# FluxamasynthShield.net
KiCad netlist of a schematic drawn in EAGLE
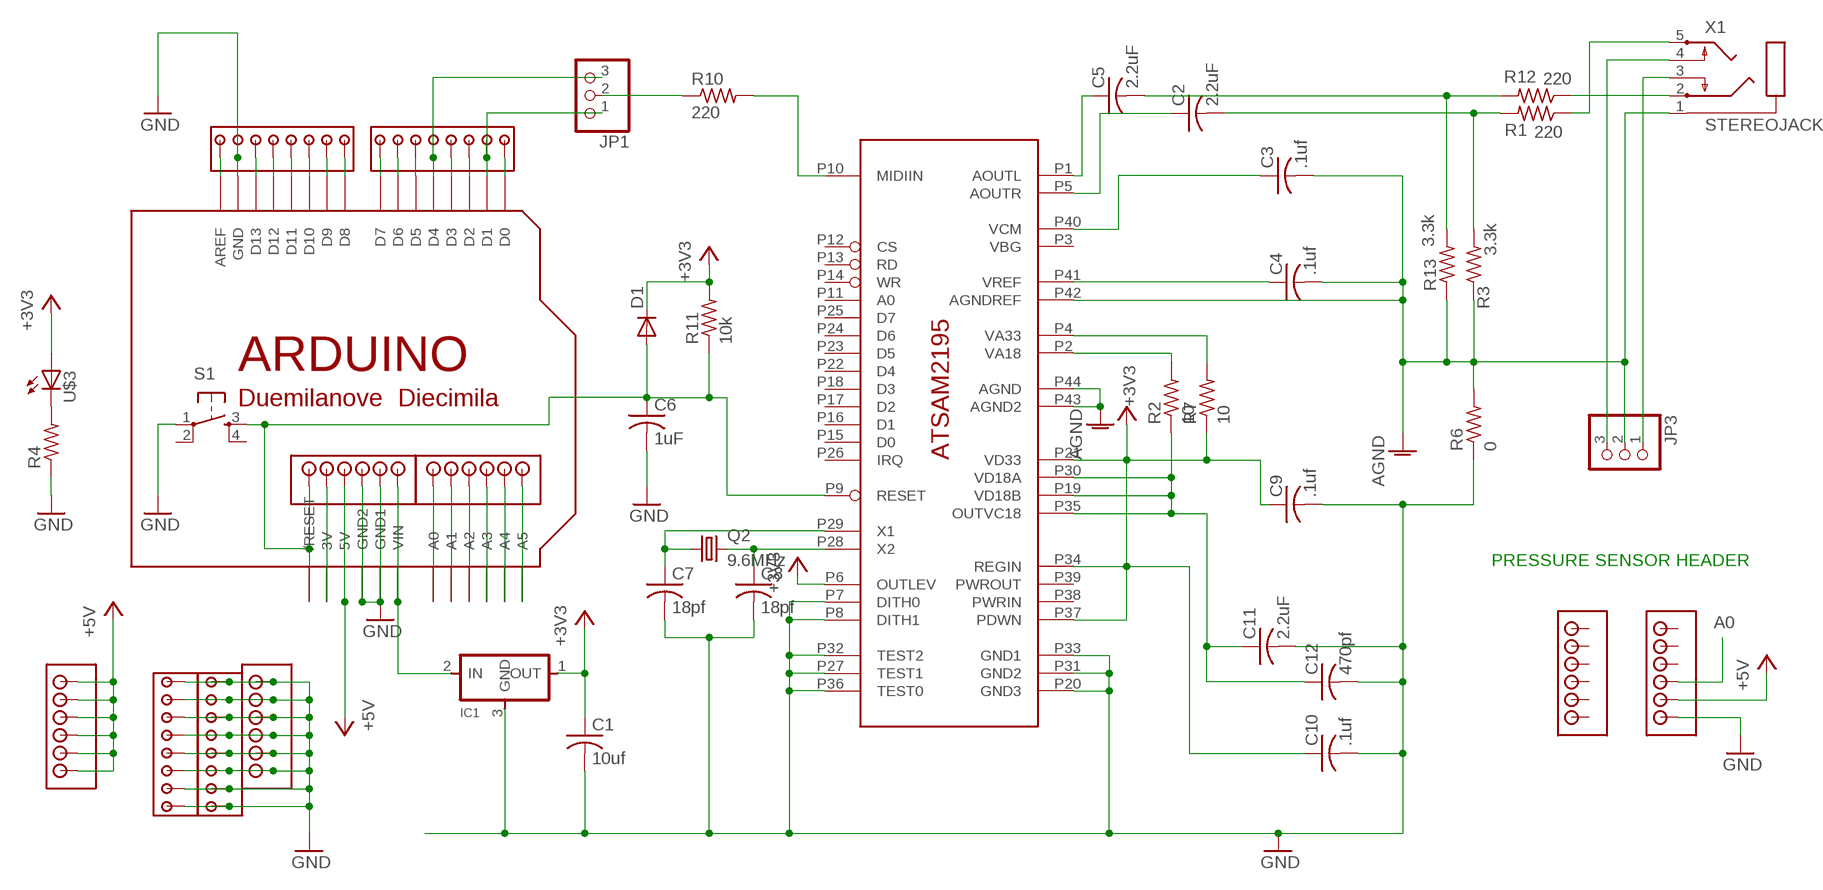
[diagram p0: schematic, sheet 1]

(export (version "E")
  (design (tool "Eeschema 10.0.6"))
  (components
    (comp (ref "C1")
      (value "10uf")
      (footprint "eagle-import:C0805")
      (libsource (lib "eagle-import") (part "C-USC0805"))
    )
    (comp (ref "C2")
      (value "2.2uF")
      (footprint "eagle-import:C0805")
      (libsource (lib "eagle-import") (part "C-USC0805"))
    )
    (comp (ref "C3")
      (value ".1uf")
      (footprint "eagle-import:C0805")
      (libsource (lib "eagle-import") (part "C-USC0805"))
    )
    (comp (ref "C4")
      (value ".1uf")
      (footprint "eagle-import:C0805")
      (libsource (lib "eagle-import") (part "C-USC0805"))
    )
    (comp (ref "C5")
      (value "2.2uF")
      (footprint "eagle-import:C0805")
      (libsource (lib "eagle-import") (part "C-USC0805"))
    )
    (comp (ref "C6")
      (value "1uF")
      (footprint "eagle-import:C0805")
      (libsource (lib "eagle-import") (part "C-USC0805"))
    )
    (comp (ref "C7")
      (value "18pf")
      (footprint "eagle-import:C0805")
      (libsource (lib "eagle-import") (part "C-USC0805"))
    )
    (comp (ref "C8")
      (value "18pf")
      (footprint "eagle-import:C0805")
      (libsource (lib "eagle-import") (part "C-USC0805"))
    )
    (comp (ref "C9")
      (value ".1uf")
      (footprint "eagle-import:C0805")
      (libsource (lib "eagle-import") (part "C-USC0805"))
    )
    (comp (ref "C10")
      (value ".1uf")
      (footprint "eagle-import:C0805")
      (libsource (lib "eagle-import") (part "C-USC0805"))
    )
    (comp (ref "C11")
      (value "2.2uF")
      (footprint "eagle-import:C0805")
      (libsource (lib "eagle-import") (part "C-USC0805"))
    )
    (comp (ref "C12")
      (value "470pf")
      (footprint "eagle-import:C0805")
      (libsource (lib "eagle-import") (part "C-USC0805"))
    )
    (comp (ref "D1")
      (value "DIODESOD123")
      (footprint "eagle-import:SOD123")
      (libsource (lib "eagle-import") (part "DIODESOD123"))
    )
    (comp (ref "IC1")
      (value "REGULATORSOT23")
      (footprint "eagle-import:SOT23")
      (libsource (lib "eagle-import") (part "REGULATORSOT23"))
    )
    (comp (ref "JP1")
      (value "PINHD-1X3")
      (footprint "eagle-import:1X03")
      (libsource (lib "eagle-import") (part "PINHD-1X3"))
    )
    (comp (ref "JP3")
      (value "PINHD-1X3")
      (footprint "eagle-import:1X03")
      (libsource (lib "eagle-import") (part "PINHD-1X3"))
    )
    (comp (ref "Q2")
      (value "9.6MHz")
      (footprint "eagle-import:TC26H")
      (libsource (lib "eagle-import") (part "CRYSTALTC26H"))
    )
    (comp (ref "R1")
      (value "220")
      (footprint "eagle-import:M0805")
      (libsource (lib "eagle-import") (part "R-US_M0805"))
    )
    (comp (ref "R2")
      (value "10")
      (footprint "eagle-import:M0805")
      (libsource (lib "eagle-import") (part "R-US_M0805"))
    )
    (comp (ref "R3")
      (value "3.3k")
      (footprint "eagle-import:M0805")
      (libsource (lib "eagle-import") (part "R-US_M0805"))
    )
    (comp (ref "R4")
      (value "R-US_M0805")
      (footprint "eagle-import:M0805")
      (libsource (lib "eagle-import") (part "R-US_M0805"))
    )
    (comp (ref "R6")
      (value "0")
      (footprint "eagle-import:M0805")
      (libsource (lib "eagle-import") (part "R-US_M0805"))
    )
    (comp (ref "R7")
      (value "10")
      (footprint "eagle-import:M0805")
      (libsource (lib "eagle-import") (part "R-US_M0805"))
    )
    (comp (ref "R10")
      (value "220")
      (footprint "eagle-import:M0805")
      (libsource (lib "eagle-import") (part "R-US_M0805"))
    )
    (comp (ref "R11")
      (value "10k")
      (footprint "eagle-import:M0805")
      (libsource (lib "eagle-import") (part "R-US_M0805"))
    )
    (comp (ref "R12")
      (value "220")
      (footprint "eagle-import:M0805")
      (libsource (lib "eagle-import") (part "R-US_M0805"))
    )
    (comp (ref "R13")
      (value "3.3k")
      (footprint "eagle-import:M0805")
      (libsource (lib "eagle-import") (part "R-US_M0805"))
    )
    (comp (ref "S1")
      (value "6MM_SWITCH6MM_SWITCH")
      (footprint "eagle-import:6MM_SWITCH")
      (libsource (lib "eagle-import") (part "6MM_SWITCH6MM_SWITCH"))
    )
    (comp (ref "U$1")
      (value "ATSAM2195")
      (footprint "eagle-import:ATSAM2195")
      (libsource (lib "eagle-import") (part "ATSAM2195"))
    )
    (comp (ref "U$2")
      (value "ARDUINODUEMILANOVE-NOHOLES")
      (footprint "eagle-import:ARDUINO-NOHOLE")
      (libsource (lib "eagle-import") (part "ARDUINODUEMILANOVE-NOHOLES"))
    )
    (comp (ref "U$3")
      (value "LED1206")
      (footprint "eagle-import:1206")
      (libsource (lib "eagle-import") (part "LED1206"))
    )
    (comp (ref "U$4")
      (value "1X6HEADER")
      (footprint "eagle-import:1X6HEADER")
      (libsource (lib "eagle-import") (part "1X6HEADER"))
    )
    (comp (ref "U$5")
      (value "1X6HEADER")
      (footprint "eagle-import:1X6HEADER")
      (libsource (lib "eagle-import") (part "1X6HEADER"))
    )
    (comp (ref "U$6")
      (value "1X8HEADER")
      (footprint "eagle-import:1X8HEADER")
      (libsource (lib "eagle-import") (part "1X8HEADER"))
    )
    (comp (ref "U$7")
      (value "1X8HEADER")
      (footprint "eagle-import:1X8HEADER")
      (libsource (lib "eagle-import") (part "1X8HEADER"))
    )
    (comp (ref "U$8")
      (value "1X6HEADER")
      (footprint "eagle-import:1X6HEADER")
      (libsource (lib "eagle-import") (part "1X6HEADER"))
    )
    (comp (ref "U$9")
      (value "1X6HEADER")
      (footprint "eagle-import:1X6HEADER")
      (libsource (lib "eagle-import") (part "1X6HEADER"))
    )
    (comp (ref "U$10")
      (value "1X8HEADER")
      (footprint "eagle-import:1X8HEADER")
      (libsource (lib "eagle-import") (part "1X8HEADER"))
    )
    (comp (ref "U$11")
      (value "1X8HEADER")
      (footprint "eagle-import:1X8HEADER")
      (libsource (lib "eagle-import") (part "1X8HEADER"))
    )
    (comp (ref "U$12")
      (value "1X6HEADER")
      (footprint "eagle-import:1X6HEADER")
      (libsource (lib "eagle-import") (part "1X6HEADER"))
    )
    (comp (ref "U$13")
      (value "1X6HEADER")
      (footprint "eagle-import:1X6HEADER")
      (libsource (lib "eagle-import") (part "1X6HEADER"))
    )
    (comp (ref "X1")
      (value "STEREOJACK")
      (footprint "eagle-import:STX3100")
      (libsource (lib "eagle-import") (part "STEREOJACK"))
    )
  )
  (nets
    (net (code "1") (name "+3V3") (class "Default")
      (node (ref "C1") (pin "1") (pinfunction "1_1") (pintype "passive"))
      (node (ref "C10") (pin "1") (pinfunction "1_1") (pintype "passive"))
      (node (ref "C9") (pin "1") (pinfunction "1_1") (pintype "passive"))
      (node (ref "D1") (pin "CATHODE") (pinfunction "C_CATHODE") (pintype "passive"))
      (node (ref "IC1") (pin "1") (pinfunction "OUT_1") (pintype "bidirectional"))
      (node (ref "R11") (pin "2") (pinfunction "2_2") (pintype "passive"))
      (node (ref "R7") (pin "1") (pinfunction "1_1") (pintype "passive"))
      (node (ref "U$1") (pin "P21") (pinfunction "VD33_P21") (pintype "bidirectional"))
      (node (ref "U$1") (pin "P34") (pinfunction "REGIN_P34") (pintype "bidirectional"))
      (node (ref "U$1") (pin "P37") (pinfunction "PDWN_P37") (pintype "bidirectional"))
      (node (ref "U$1") (pin "P6") (pinfunction "OUTLEV_P6") (pintype "bidirectional"))
      (node (ref "U$3") (pin "1") (pinfunction "A_1") (pintype "passive"))
    )
    (net (code "2") (name "+5V") (class "Default")
      (node (ref "U$12") (pin "P$2") (pinfunction "P$2_P$2") (pintype "bidirectional"))
      (node (ref "U$2") (pin "5V") (pinfunction "5V_5V") (pintype "power_in"))
      (node (ref "U$4") (pin "P$3") (pinfunction "P$3_P$3") (pintype "bidirectional"))
      (node (ref "U$9") (pin "P$1") (pinfunction "P$1_P$1") (pintype "bidirectional"))
      (node (ref "U$9") (pin "P$2") (pinfunction "P$2_P$2") (pintype "bidirectional"))
      (node (ref "U$9") (pin "P$3") (pinfunction "P$3_P$3") (pintype "bidirectional"))
      (node (ref "U$9") (pin "P$4") (pinfunction "P$4_P$4") (pintype "bidirectional"))
      (node (ref "U$9") (pin "P$5") (pinfunction "P$5_P$5") (pintype "bidirectional"))
      (node (ref "U$9") (pin "P$6") (pinfunction "P$6_P$6") (pintype "bidirectional"))
    )
    (net (code "3") (name "/A0") (class "Default")
      (node (ref "U$12") (pin "P$3") (pinfunction "P$3_P$3") (pintype "bidirectional"))
      (node (ref "U$2") (pin "A0") (pinfunction "A0_A0") (pintype "bidirectional"))
      (node (ref "U$5") (pin "P$1") (pinfunction "P$1_P$1") (pintype "bidirectional"))
    )
    (net (code "4") (name "AGND") (class "Default")
      (node (ref "C3") (pin "2") (pinfunction "2_2") (pintype "passive"))
      (node (ref "C4") (pin "2") (pinfunction "2_2") (pintype "passive"))
      (node (ref "JP3") (pin "2") (pinfunction "2_2") (pintype "passive"))
      (node (ref "R13") (pin "1") (pinfunction "1_1") (pintype "passive"))
      (node (ref "R3") (pin "1") (pinfunction "1_1") (pintype "passive"))
      (node (ref "R6") (pin "2") (pinfunction "2_2") (pintype "passive"))
      (node (ref "U$1") (pin "P42") (pinfunction "AGNDREF_P42") (pintype "bidirectional"))
      (node (ref "U$1") (pin "P43") (pinfunction "AGND2_P43") (pintype "bidirectional"))
      (node (ref "U$1") (pin "P44") (pinfunction "AGND_P44") (pintype "bidirectional"))
      (node (ref "X1") (pin "1") (pinfunction "1_1") (pintype "passive"))
    )
    (net (code "5") (name "GND") (class "Default")
      (node (ref "C1") (pin "2") (pinfunction "2_2") (pintype "passive"))
      (node (ref "C10") (pin "2") (pinfunction "2_2") (pintype "passive"))
      (node (ref "C11") (pin "2") (pinfunction "2_2") (pintype "passive"))
      (node (ref "C12") (pin "2") (pinfunction "2_2") (pintype "passive"))
      (node (ref "C6") (pin "2") (pinfunction "2_2") (pintype "passive"))
      (node (ref "C7") (pin "2") (pinfunction "2_2") (pintype "passive"))
      (node (ref "C8") (pin "2") (pinfunction "2_2") (pintype "passive"))
      (node (ref "C9") (pin "2") (pinfunction "2_2") (pintype "passive"))
      (node (ref "IC1") (pin "3") (pinfunction "GND_3") (pintype "bidirectional"))
      (node (ref "R4") (pin "1") (pinfunction "1_1") (pintype "passive"))
      (node (ref "R6") (pin "1") (pinfunction "1_1") (pintype "passive"))
      (node (ref "S1") (pin "1") (pinfunction "P_1") (pintype "passive"))
      (node (ref "U$1") (pin "P20") (pinfunction "GND3_P20") (pintype "bidirectional"))
      (node (ref "U$1") (pin "P27") (pinfunction "TEST1_P27") (pintype "bidirectional"))
      (node (ref "U$1") (pin "P31") (pinfunction "GND2_P31") (pintype "bidirectional"))
      (node (ref "U$1") (pin "P32") (pinfunction "TEST2_P32") (pintype "bidirectional"))
      (node (ref "U$1") (pin "P33") (pinfunction "GND1_P33") (pintype "bidirectional"))
      (node (ref "U$1") (pin "P36") (pinfunction "TEST0_P36") (pintype "bidirectional"))
      (node (ref "U$1") (pin "P7") (pinfunction "DITH0_P7") (pintype "bidirectional"))
      (node (ref "U$1") (pin "P8") (pinfunction "DITH1_P8") (pintype "bidirectional"))
      (node (ref "U$10") (pin "P$1") (pinfunction "P$1_P$1") (pintype "bidirectional"))
      (node (ref "U$10") (pin "P$2") (pinfunction "P$2_P$2") (pintype "bidirectional"))
      (node (ref "U$10") (pin "P$3") (pinfunction "P$3_P$3") (pintype "bidirectional"))
      (node (ref "U$10") (pin "P$4") (pinfunction "P$4_P$4") (pintype "bidirectional"))
      (node (ref "U$10") (pin "P$5") (pinfunction "P$5_P$5") (pintype "bidirectional"))
      (node (ref "U$10") (pin "P$6") (pinfunction "P$6_P$6") (pintype "bidirectional"))
      (node (ref "U$10") (pin "P$7") (pinfunction "P$7_P$7") (pintype "bidirectional"))
      (node (ref "U$10") (pin "P$8") (pinfunction "P$8_P$8") (pintype "bidirectional"))
      (node (ref "U$11") (pin "P$1") (pinfunction "P$1_P$1") (pintype "bidirectional"))
      (node (ref "U$11") (pin "P$2") (pinfunction "P$2_P$2") (pintype "bidirectional"))
      (node (ref "U$11") (pin "P$3") (pinfunction "P$3_P$3") (pintype "bidirectional"))
      (node (ref "U$11") (pin "P$4") (pinfunction "P$4_P$4") (pintype "bidirectional"))
      (node (ref "U$11") (pin "P$5") (pinfunction "P$5_P$5") (pintype "bidirectional"))
      (node (ref "U$11") (pin "P$6") (pinfunction "P$6_P$6") (pintype "bidirectional"))
      (node (ref "U$11") (pin "P$7") (pinfunction "P$7_P$7") (pintype "bidirectional"))
      (node (ref "U$11") (pin "P$8") (pinfunction "P$8_P$8") (pintype "bidirectional"))
      (node (ref "U$12") (pin "P$1") (pinfunction "P$1_P$1") (pintype "bidirectional"))
      (node (ref "U$2") (pin "GND") (pinfunction "GND_GND") (pintype "power_in"))
      (node (ref "U$2") (pin "GND1") (pinfunction "GND1_GND1") (pintype "power_in"))
      (node (ref "U$2") (pin "GND2") (pinfunction "GND2_GND2") (pintype "power_in"))
      (node (ref "U$4") (pin "P$4") (pinfunction "P$4_P$4") (pintype "bidirectional"))
      (node (ref "U$4") (pin "P$5") (pinfunction "P$5_P$5") (pintype "bidirectional"))
      (node (ref "U$6") (pin "P$2") (pinfunction "P$2_P$2") (pintype "bidirectional"))
      (node (ref "U$8") (pin "P$1") (pinfunction "P$1_P$1") (pintype "bidirectional"))
      (node (ref "U$8") (pin "P$2") (pinfunction "P$2_P$2") (pintype "bidirectional"))
      (node (ref "U$8") (pin "P$3") (pinfunction "P$3_P$3") (pintype "bidirectional"))
      (node (ref "U$8") (pin "P$4") (pinfunction "P$4_P$4") (pintype "bidirectional"))
      (node (ref "U$8") (pin "P$5") (pinfunction "P$5_P$5") (pintype "bidirectional"))
      (node (ref "U$8") (pin "P$6") (pinfunction "P$6_P$6") (pintype "bidirectional"))
    )
    (net (code "6") (name "Net-(C2-Pad2)") (class "Default")
      (node (ref "C2") (pin "2") (pinfunction "2_2") (pintype "passive"))
      (node (ref "R1") (pin "2") (pinfunction "2_2") (pintype "passive"))
      (node (ref "R3") (pin "2") (pinfunction "2_2") (pintype "passive"))
    )
    (net (code "7") (name "Net-(C5-Pad2)") (class "Default")
      (node (ref "C5") (pin "2") (pinfunction "2_2") (pintype "passive"))
      (node (ref "R12") (pin "2") (pinfunction "2_2") (pintype "passive"))
      (node (ref "R13") (pin "2") (pinfunction "2_2") (pintype "passive"))
    )
    (net (code "8") (name "Net-(D1-A)") (class "Default")
      (node (ref "C6") (pin "1") (pinfunction "1_1") (pintype "passive"))
      (node (ref "D1") (pin "ANODE") (pinfunction "A_ANODE") (pintype "passive"))
      (node (ref "R11") (pin "1") (pinfunction "1_1") (pintype "passive"))
      (node (ref "S1") (pin "3") (pinfunction "S_3") (pintype "passive"))
      (node (ref "U$1") (pin "P9") (pinfunction "RESET_P9") (pintype "bidirectional"))
      (node (ref "U$2") (pin "RESET") (pinfunction "/RESET_RESET") (pintype "bidirectional"))
      (node (ref "U$4") (pin "P$1") (pinfunction "P$1_P$1") (pintype "bidirectional"))
    )
    (net (code "9") (name "Net-(IC1-IN)") (class "Default")
      (node (ref "IC1") (pin "2") (pinfunction "IN_2") (pintype "bidirectional"))
      (node (ref "U$2") (pin "VIN") (pinfunction "VIN_VIN") (pintype "power_in"))
      (node (ref "U$4") (pin "P$6") (pinfunction "P$6_P$6") (pintype "bidirectional"))
    )
    (net (code "10") (name "Net-(JP1-Pad1)") (class "Default")
      (node (ref "JP1") (pin "1") (pinfunction "1_1") (pintype "passive"))
      (node (ref "U$2") (pin "D1") (pinfunction "D1_D1") (pintype "bidirectional"))
      (node (ref "U$7") (pin "P$7") (pinfunction "P$7_P$7") (pintype "bidirectional"))
    )
    (net (code "11") (name "Net-(JP1-Pad2)") (class "Default")
      (node (ref "JP1") (pin "2") (pinfunction "2_2") (pintype "passive"))
      (node (ref "R10") (pin "1") (pinfunction "1_1") (pintype "passive"))
    )
    (net (code "12") (name "Net-(JP1-Pad3)") (class "Default")
      (node (ref "JP1") (pin "3") (pinfunction "3_3") (pintype "passive"))
      (node (ref "U$2") (pin "D4") (pinfunction "D4_D4") (pintype "bidirectional"))
      (node (ref "U$7") (pin "P$4") (pinfunction "P$4_P$4") (pintype "bidirectional"))
    )
    (net (code "13") (name "Net-(JP3-Pad1)") (class "Default")
      (node (ref "JP3") (pin "1") (pinfunction "1_1") (pintype "passive"))
      (node (ref "X1") (pin "3") (pinfunction "3_3") (pintype "passive"))
    )
    (net (code "14") (name "Net-(JP3-Pad3)") (class "Default")
      (node (ref "JP3") (pin "3") (pinfunction "3_3") (pintype "passive"))
      (node (ref "X1") (pin "4") (pinfunction "4_4") (pintype "passive"))
    )
    (net (code "15") (name "Net-(R1-Pad1)") (class "Default")
      (node (ref "R1") (pin "1") (pinfunction "1_1") (pintype "passive"))
      (node (ref "X1") (pin "5") (pinfunction "5_5") (pintype "passive"))
    )
    (net (code "16") (name "Net-(R12-Pad1)") (class "Default")
      (node (ref "R12") (pin "1") (pinfunction "1_1") (pintype "passive"))
      (node (ref "X1") (pin "2") (pinfunction "2_2") (pintype "passive"))
    )
    (net (code "17") (name "Net-(U$1-AOUTL)") (class "Default")
      (node (ref "C5") (pin "1") (pinfunction "1_1") (pintype "passive"))
      (node (ref "U$1") (pin "P1") (pinfunction "AOUTL_P1") (pintype "bidirectional"))
    )
    (net (code "18") (name "Net-(U$1-AOUTR)") (class "Default")
      (node (ref "C2") (pin "1") (pinfunction "1_1") (pintype "passive"))
      (node (ref "U$1") (pin "P5") (pinfunction "AOUTR_P5") (pintype "bidirectional"))
    )
    (net (code "19") (name "Net-(U$1-MIDIIN)") (class "Default")
      (node (ref "R10") (pin "2") (pinfunction "2_2") (pintype "passive"))
      (node (ref "U$1") (pin "P10") (pinfunction "MIDIIN_P10") (pintype "bidirectional"))
    )
    (net (code "20") (name "Net-(U$1-OUTVC18)") (class "Default")
      (node (ref "C11") (pin "1") (pinfunction "1_1") (pintype "passive"))
      (node (ref "C12") (pin "1") (pinfunction "1_1") (pintype "passive"))
      (node (ref "R2") (pin "1") (pinfunction "1_1") (pintype "passive"))
      (node (ref "U$1") (pin "P19") (pinfunction "VD18B_P19") (pintype "bidirectional"))
      (node (ref "U$1") (pin "P30") (pinfunction "VD18A_P30") (pintype "bidirectional"))
      (node (ref "U$1") (pin "P35") (pinfunction "OUTVC18_P35") (pintype "bidirectional"))
    )
    (net (code "21") (name "Net-(U$1-VA18)") (class "Default")
      (node (ref "R2") (pin "2") (pinfunction "2_2") (pintype "passive"))
      (node (ref "U$1") (pin "P2") (pinfunction "VA18_P2") (pintype "bidirectional"))
    )
    (net (code "22") (name "Net-(U$1-VA33)") (class "Default")
      (node (ref "R7") (pin "2") (pinfunction "2_2") (pintype "passive"))
      (node (ref "U$1") (pin "P4") (pinfunction "VA33_P4") (pintype "bidirectional"))
    )
    (net (code "23") (name "Net-(U$1-VCM)") (class "Default")
      (node (ref "C3") (pin "1") (pinfunction "1_1") (pintype "passive"))
      (node (ref "U$1") (pin "P40") (pinfunction "VCM_P40") (pintype "bidirectional"))
    )
    (net (code "24") (name "Net-(U$1-VREF)") (class "Default")
      (node (ref "C4") (pin "1") (pinfunction "1_1") (pintype "passive"))
      (node (ref "U$1") (pin "P41") (pinfunction "VREF_P41") (pintype "bidirectional"))
    )
    (net (code "25") (name "Net-(U$1-X1)") (class "Default")
      (node (ref "C7") (pin "1") (pinfunction "1_1") (pintype "passive"))
      (node (ref "Q2") (pin "1") (pinfunction "1_1") (pintype "passive"))
      (node (ref "U$1") (pin "P29") (pinfunction "X1_P29") (pintype "bidirectional"))
    )
    (net (code "26") (name "Net-(U$1-X2)") (class "Default")
      (node (ref "C8") (pin "1") (pinfunction "1_1") (pintype "passive"))
      (node (ref "Q2") (pin "2") (pinfunction "2_2") (pintype "passive"))
      (node (ref "U$1") (pin "P28") (pinfunction "X2_P28") (pintype "bidirectional"))
    )
    (net (code "27") (name "Net-(U$2-Pad3V)") (class "Default")
      (node (ref "U$2") (pin "3V") (pinfunction "3V_3V") (pintype "power_in"))
      (node (ref "U$4") (pin "P$2") (pinfunction "P$2_P$2") (pintype "bidirectional"))
    )
    (net (code "28") (name "Net-(U$2-PadA1)") (class "Default")
      (node (ref "U$2") (pin "A1") (pinfunction "A1_A1") (pintype "bidirectional"))
      (node (ref "U$5") (pin "P$2") (pinfunction "P$2_P$2") (pintype "bidirectional"))
    )
    (net (code "29") (name "Net-(U$2-PadA2)") (class "Default")
      (node (ref "U$2") (pin "A2") (pinfunction "A2_A2") (pintype "bidirectional"))
      (node (ref "U$5") (pin "P$3") (pinfunction "P$3_P$3") (pintype "bidirectional"))
    )
    (net (code "30") (name "Net-(U$2-PadA3)") (class "Default")
      (node (ref "U$2") (pin "A3") (pinfunction "A3_A3") (pintype "bidirectional"))
      (node (ref "U$5") (pin "P$4") (pinfunction "P$4_P$4") (pintype "bidirectional"))
    )
    (net (code "31") (name "Net-(U$2-PadA4)") (class "Default")
      (node (ref "U$2") (pin "A4") (pinfunction "A4_A4") (pintype "bidirectional"))
      (node (ref "U$5") (pin "P$5") (pinfunction "P$5_P$5") (pintype "bidirectional"))
    )
    (net (code "32") (name "Net-(U$2-PadA5)") (class "Default")
      (node (ref "U$2") (pin "A5") (pinfunction "A5_A5") (pintype "bidirectional"))
      (node (ref "U$5") (pin "P$6") (pinfunction "P$6_P$6") (pintype "bidirectional"))
    )
    (net (code "33") (name "Net-(U$2-PadAREF)") (class "Default")
      (node (ref "U$2") (pin "AREF") (pinfunction "AREF_AREF") (pintype "bidirectional"))
      (node (ref "U$6") (pin "P$1") (pinfunction "P$1_P$1") (pintype "bidirectional"))
    )
    (net (code "34") (name "Net-(U$2-PadD0)") (class "Default")
      (node (ref "U$2") (pin "D0") (pinfunction "D0_D0") (pintype "bidirectional"))
      (node (ref "U$7") (pin "P$8") (pinfunction "P$8_P$8") (pintype "bidirectional"))
    )
    (net (code "35") (name "Net-(U$2-PadD2)") (class "Default")
      (node (ref "U$2") (pin "D2") (pinfunction "D2_D2") (pintype "bidirectional"))
      (node (ref "U$7") (pin "P$6") (pinfunction "P$6_P$6") (pintype "bidirectional"))
    )
    (net (code "36") (name "Net-(U$2-PadD3)") (class "Default")
      (node (ref "U$2") (pin "D3") (pinfunction "D3_D3") (pintype "bidirectional"))
      (node (ref "U$7") (pin "P$5") (pinfunction "P$5_P$5") (pintype "bidirectional"))
    )
    (net (code "37") (name "Net-(U$2-PadD5)") (class "Default")
      (node (ref "U$2") (pin "D5") (pinfunction "D5_D5") (pintype "bidirectional"))
      (node (ref "U$7") (pin "P$3") (pinfunction "P$3_P$3") (pintype "bidirectional"))
    )
    (net (code "38") (name "Net-(U$2-PadD6)") (class "Default")
      (node (ref "U$2") (pin "D6") (pinfunction "D6_D6") (pintype "bidirectional"))
      (node (ref "U$7") (pin "P$2") (pinfunction "P$2_P$2") (pintype "bidirectional"))
    )
    (net (code "39") (name "Net-(U$2-PadD7)") (class "Default")
      (node (ref "U$2") (pin "D7") (pinfunction "D7_D7") (pintype "bidirectional"))
      (node (ref "U$7") (pin "P$1") (pinfunction "P$1_P$1") (pintype "bidirectional"))
    )
    (net (code "40") (name "Net-(U$2-PadD8)") (class "Default")
      (node (ref "U$2") (pin "D8") (pinfunction "D8_D8") (pintype "bidirectional"))
      (node (ref "U$6") (pin "P$8") (pinfunction "P$8_P$8") (pintype "bidirectional"))
    )
    (net (code "41") (name "Net-(U$2-PadD9)") (class "Default")
      (node (ref "U$2") (pin "D9") (pinfunction "D9_D9") (pintype "bidirectional"))
      (node (ref "U$6") (pin "P$7") (pinfunction "P$7_P$7") (pintype "bidirectional"))
    )
    (net (code "42") (name "Net-(U$2-PadD10)") (class "Default")
      (node (ref "U$2") (pin "D10") (pinfunction "D10_D10") (pintype "bidirectional"))
      (node (ref "U$6") (pin "P$6") (pinfunction "P$6_P$6") (pintype "bidirectional"))
    )
    (net (code "43") (name "Net-(U$2-PadD11)") (class "Default")
      (node (ref "U$2") (pin "D11") (pinfunction "D11_D11") (pintype "bidirectional"))
      (node (ref "U$6") (pin "P$5") (pinfunction "P$5_P$5") (pintype "bidirectional"))
    )
    (net (code "44") (name "Net-(U$2-PadD12)") (class "Default")
      (node (ref "U$2") (pin "D12") (pinfunction "D12_D12") (pintype "bidirectional"))
      (node (ref "U$6") (pin "P$4") (pinfunction "P$4_P$4") (pintype "bidirectional"))
    )
    (net (code "45") (name "Net-(U$2-PadD13)") (class "Default")
      (node (ref "U$2") (pin "D13") (pinfunction "D13_D13") (pintype "bidirectional"))
      (node (ref "U$6") (pin "P$3") (pinfunction "P$3_P$3") (pintype "bidirectional"))
    )
    (net (code "46") (name "Net-(U$3-C)") (class "Default")
      (node (ref "R4") (pin "2") (pinfunction "2_2") (pintype "passive"))
      (node (ref "U$3") (pin "2") (pinfunction "C_2") (pintype "passive"))
    )
    (net (code "47") (name "unconnected-(S1-P1-Pad2)") (class "Default")
      (node (ref "S1") (pin "2") (pinfunction "P1_2") (pintype "passive"))
    )
    (net (code "48") (name "unconnected-(S1-S1-Pad4)") (class "Default")
      (node (ref "S1") (pin "4") (pinfunction "S1_4") (pintype "passive"))
    )
    (net (code "49") (name "unconnected-(U$1-A0-PadP11)") (class "Default")
      (node (ref "U$1") (pin "P11") (pinfunction "A0_P11") (pintype "bidirectional"))
    )
    (net (code "50") (name "unconnected-(U$1-CS-PadP12)") (class "Default")
      (node (ref "U$1") (pin "P12") (pinfunction "CS_P12") (pintype "bidirectional"))
    )
    (net (code "51") (name "unconnected-(U$1-D0-PadP15)") (class "Default")
      (node (ref "U$1") (pin "P15") (pinfunction "D0_P15") (pintype "bidirectional"))
    )
    (net (code "52") (name "unconnected-(U$1-D1-PadP16)") (class "Default")
      (node (ref "U$1") (pin "P16") (pinfunction "D1_P16") (pintype "bidirectional"))
    )
    (net (code "53") (name "unconnected-(U$1-D2-PadP17)") (class "Default")
      (node (ref "U$1") (pin "P17") (pinfunction "D2_P17") (pintype "bidirectional"))
    )
    (net (code "54") (name "unconnected-(U$1-D3-PadP18)") (class "Default")
      (node (ref "U$1") (pin "P18") (pinfunction "D3_P18") (pintype "bidirectional"))
    )
    (net (code "55") (name "unconnected-(U$1-D4-PadP22)") (class "Default")
      (node (ref "U$1") (pin "P22") (pinfunction "D4_P22") (pintype "bidirectional"))
    )
    (net (code "56") (name "unconnected-(U$1-D5-PadP23)") (class "Default")
      (node (ref "U$1") (pin "P23") (pinfunction "D5_P23") (pintype "bidirectional"))
    )
    (net (code "57") (name "unconnected-(U$1-D6-PadP24)") (class "Default")
      (node (ref "U$1") (pin "P24") (pinfunction "D6_P24") (pintype "bidirectional"))
    )
    (net (code "58") (name "unconnected-(U$1-D7-PadP25)") (class "Default")
      (node (ref "U$1") (pin "P25") (pinfunction "D7_P25") (pintype "bidirectional"))
    )
    (net (code "59") (name "unconnected-(U$1-IRQ-PadP26)") (class "Default")
      (node (ref "U$1") (pin "P26") (pinfunction "IRQ_P26") (pintype "bidirectional"))
    )
    (net (code "60") (name "unconnected-(U$1-PWRIN-PadP38)") (class "Default")
      (node (ref "U$1") (pin "P38") (pinfunction "PWRIN_P38") (pintype "bidirectional"))
    )
    (net (code "61") (name "unconnected-(U$1-PWROUT-PadP39)") (class "Default")
      (node (ref "U$1") (pin "P39") (pinfunction "PWROUT_P39") (pintype "bidirectional"))
    )
    (net (code "62") (name "unconnected-(U$1-RD-PadP13)") (class "Default")
      (node (ref "U$1") (pin "P13") (pinfunction "RD_P13") (pintype "bidirectional"))
    )
    (net (code "63") (name "unconnected-(U$1-VBG-PadP3)") (class "Default")
      (node (ref "U$1") (pin "P3") (pinfunction "VBG_P3") (pintype "bidirectional"))
    )
    (net (code "64") (name "unconnected-(U$1-WR-PadP14)") (class "Default")
      (node (ref "U$1") (pin "P14") (pinfunction "WR_P14") (pintype "bidirectional"))
    )
    (net (code "65") (name "unconnected-(U$12-PadP$4)") (class "Default")
      (node (ref "U$12") (pin "P$4") (pinfunction "P$4_P$4") (pintype "bidirectional"))
    )
    (net (code "66") (name "unconnected-(U$12-PadP$5)") (class "Default")
      (node (ref "U$12") (pin "P$5") (pinfunction "P$5_P$5") (pintype "bidirectional"))
    )
    (net (code "67") (name "unconnected-(U$12-PadP$6)") (class "Default")
      (node (ref "U$12") (pin "P$6") (pinfunction "P$6_P$6") (pintype "bidirectional"))
    )
    (net (code "68") (name "unconnected-(U$13-PadP$1)") (class "Default")
      (node (ref "U$13") (pin "P$1") (pinfunction "P$1_P$1") (pintype "bidirectional"))
    )
    (net (code "69") (name "unconnected-(U$13-PadP$2)") (class "Default")
      (node (ref "U$13") (pin "P$2") (pinfunction "P$2_P$2") (pintype "bidirectional"))
    )
    (net (code "70") (name "unconnected-(U$13-PadP$3)") (class "Default")
      (node (ref "U$13") (pin "P$3") (pinfunction "P$3_P$3") (pintype "bidirectional"))
    )
    (net (code "71") (name "unconnected-(U$13-PadP$4)") (class "Default")
      (node (ref "U$13") (pin "P$4") (pinfunction "P$4_P$4") (pintype "bidirectional"))
    )
    (net (code "72") (name "unconnected-(U$13-PadP$5)") (class "Default")
      (node (ref "U$13") (pin "P$5") (pinfunction "P$5_P$5") (pintype "bidirectional"))
    )
    (net (code "73") (name "unconnected-(U$13-PadP$6)") (class "Default")
      (node (ref "U$13") (pin "P$6") (pinfunction "P$6_P$6") (pintype "bidirectional"))
    )
  )
)
